# Sheet1.net
KiCad netlist of a schematic drawn in Altium Designer
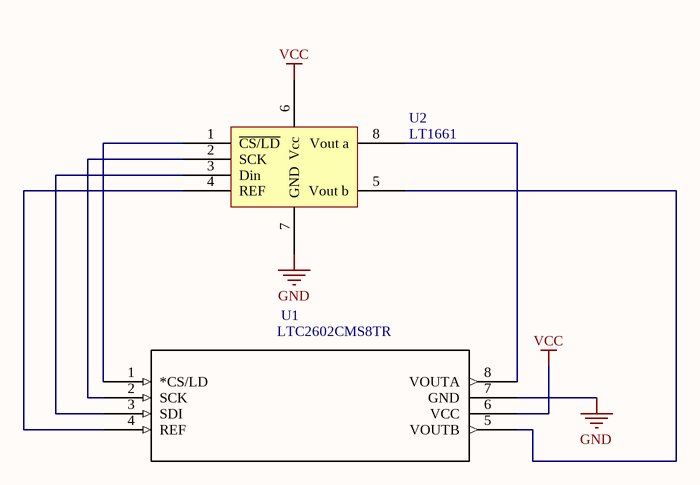
[diagram p0: Sheet1.SchDoc]

(export (version "E")
  (design (tool "Eeschema 10.0.6"))
  (components
    (comp (ref "U1")
      (value "LTC2602CMS8TR")
      (footprint "MSOP-8_MS")
      (description "Ic Dac 16bit Dual r-r Vout 8msop")
      (fields (field (name "MF") "Linear Technology") (field (name "MP") "LTC2602CMS8#TR"))
      (libsource (lib "LTC2602CMS8TR") (part "LTC2602CMS8TR"))
    )
    (comp (ref "U2") (value "LT1661") (footprint "DIP-8") (libsource (lib "ECE LIB new") (part "LT1661")))
  )
  (nets
    (net (code "1") (name "GND") (class "Default")
      (node (ref "U1") (pin "7") (pinfunction "GND_7") (pintype "power_in"))
      (node (ref "U2") (pin "7") (pinfunction "GND_7") (pintype "passive"))
    )
    (net (code "2") (name "Net-(U1-*CS{slash}LD)") (class "Default")
      (node (ref "U1") (pin "1") (pinfunction "*CS/LD_1") (pintype "input"))
      (node (ref "U2") (pin "1") (pinfunction "~{CS/LD}_1") (pintype "passive"))
    )
    (net (code "3") (name "Net-(U1-REF)") (class "Default")
      (node (ref "U1") (pin "4") (pinfunction "REF_4") (pintype "input"))
      (node (ref "U2") (pin "4") (pinfunction "REF_4") (pintype "passive"))
    )
    (net (code "4") (name "Net-(U1-SCK)") (class "Default")
      (node (ref "U1") (pin "2") (pinfunction "SCK_2") (pintype "input"))
      (node (ref "U2") (pin "2") (pinfunction "SCK_2") (pintype "passive"))
    )
    (net (code "5") (name "Net-(U1-SDI)") (class "Default")
      (node (ref "U1") (pin "3") (pinfunction "SDI_3") (pintype "input"))
      (node (ref "U2") (pin "3") (pinfunction "Din_3") (pintype "passive"))
    )
    (net (code "6") (name "Net-(U1-VOUTA)") (class "Default")
      (node (ref "U1") (pin "8") (pinfunction "VOUTA_8") (pintype "output"))
      (node (ref "U2") (pin "8") (pinfunction "Vout_a_8") (pintype "passive"))
    )
    (net (code "7") (name "Net-(U1-VOUTB)") (class "Default")
      (node (ref "U1") (pin "5") (pinfunction "VOUTB_5") (pintype "output"))
      (node (ref "U2") (pin "5") (pinfunction "Vout_b_5") (pintype "passive"))
    )
    (net (code "8") (name "VCC") (class "Default")
      (node (ref "U1") (pin "6") (pinfunction "VCC_6") (pintype "power_in"))
      (node (ref "U2") (pin "6") (pinfunction "Vcc_6") (pintype "passive"))
    )
  )
)
